# 4-Connectors.net
KiCad netlist of a schematic drawn in Altium Designer
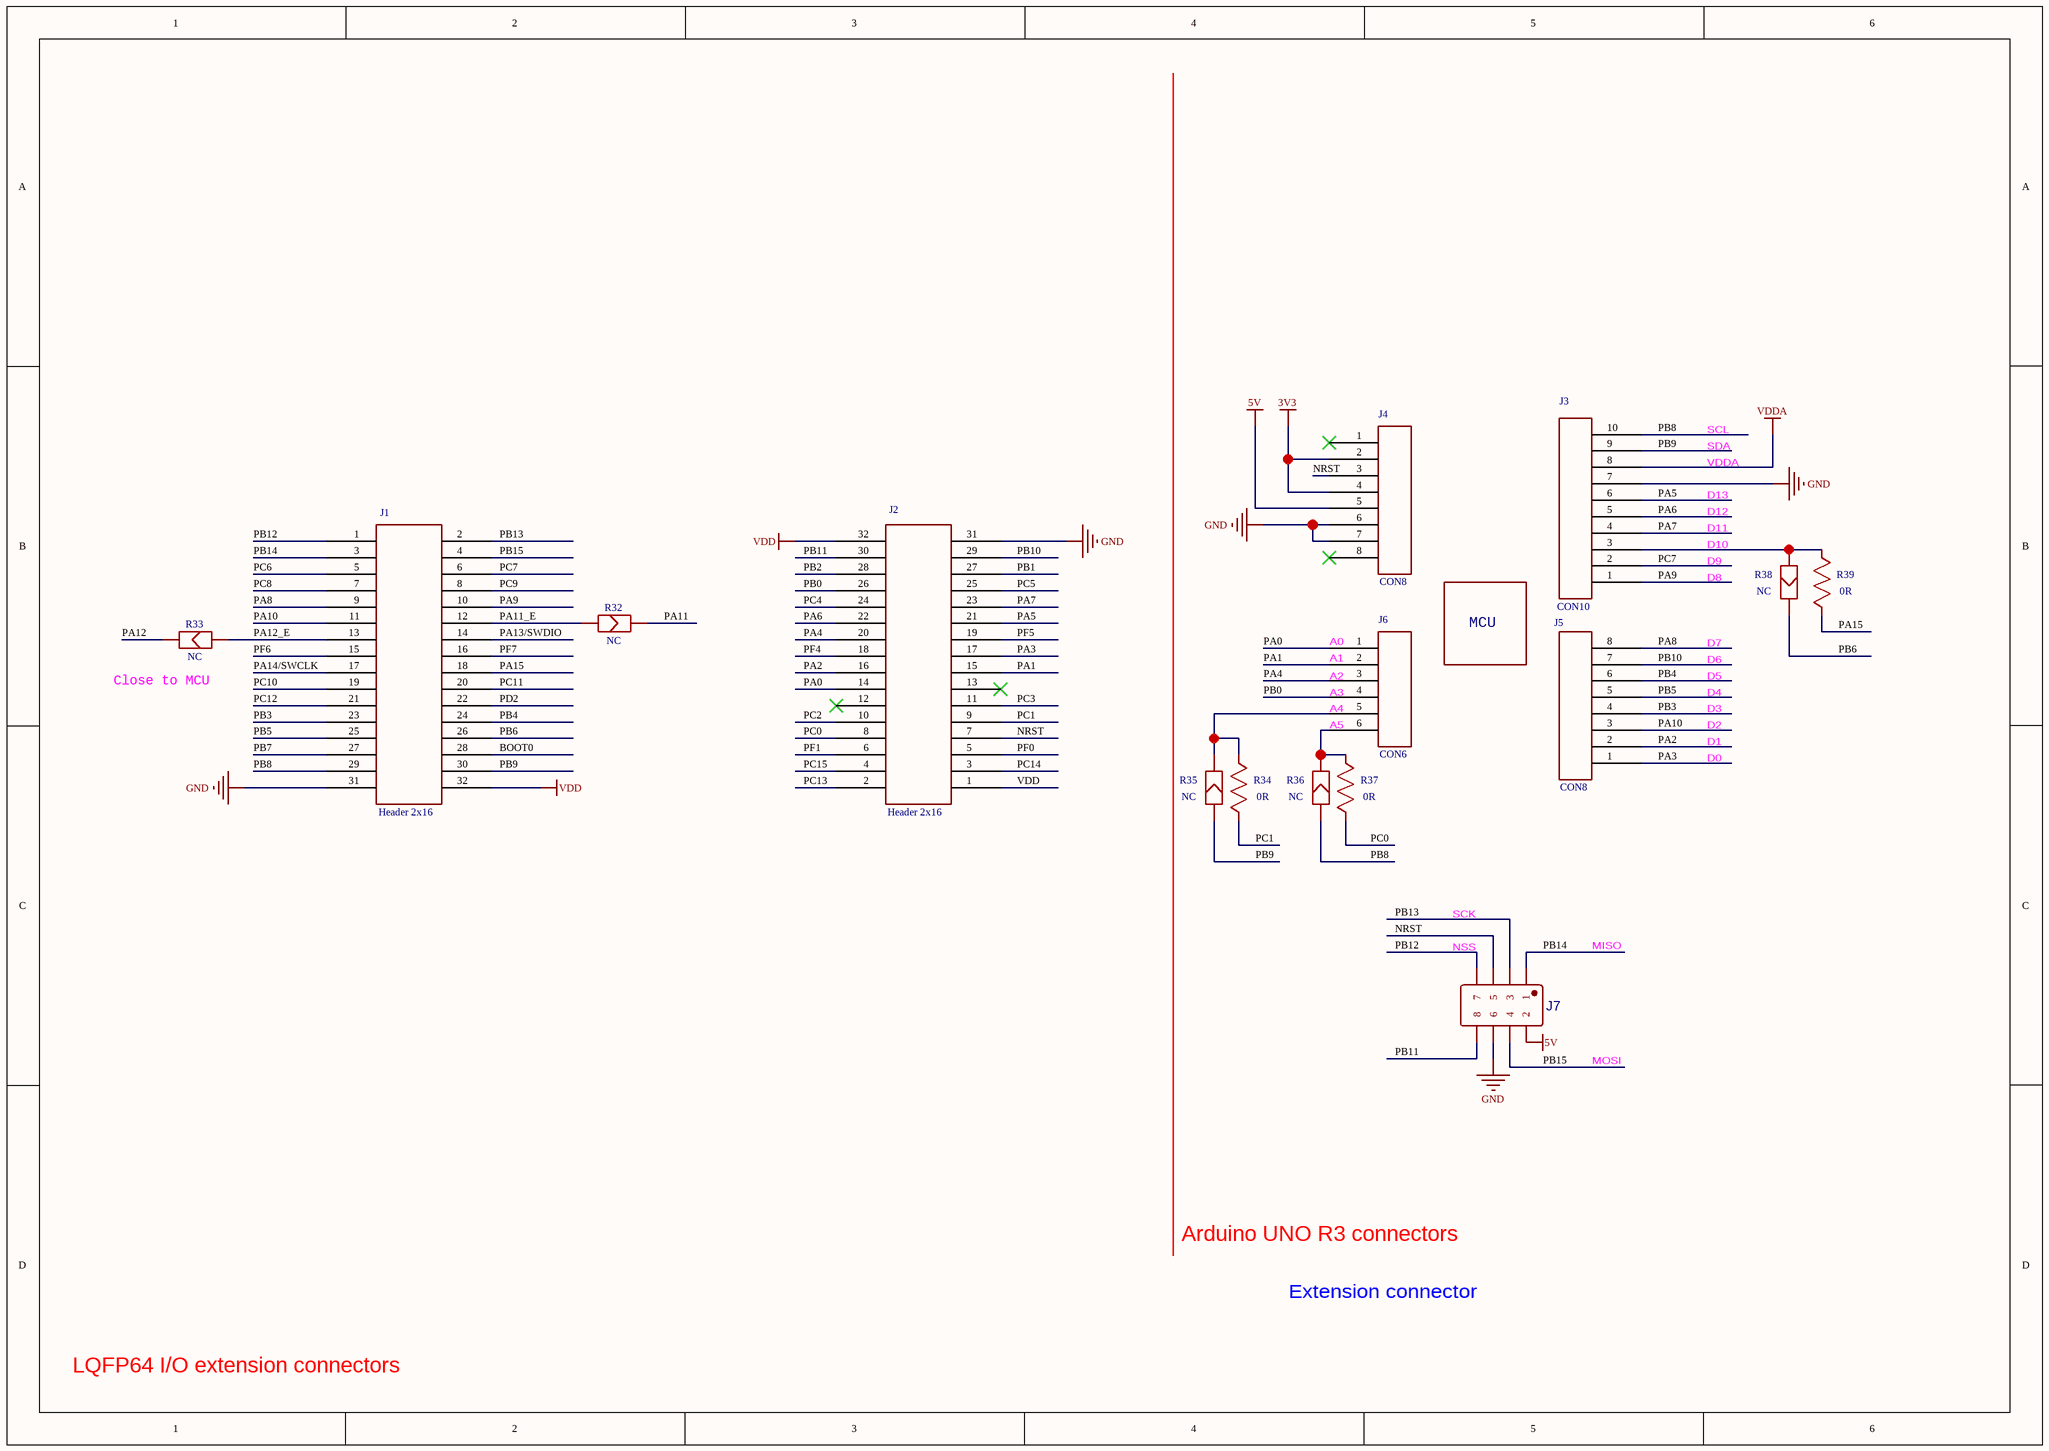
[diagram p0: 4-Connectors.schdoc]

(export (version "E")
  (design (tool "Eeschema 10.0.6"))
  (components
    (comp (ref "J1") (value "Header 2x16") (libsource (lib "altium-import") (part "root_0_Header 2x16_")))
    (comp (ref "J2") (value "Header 2x16") (libsource (lib "altium-import") (part "root_2_Header 2x16_")))
    (comp (ref "J3") (value "CON10") (libsource (lib "altium-import") (part "root_2_CON10_")))
    (comp (ref "J4") (value "CON8") (libsource (lib "altium-import") (part "root_0_CON8_")))
    (comp (ref "J5") (value "CON8") (libsource (lib "altium-import") (part "root_2_CON8_")))
    (comp (ref "J6") (value "CON6") (libsource (lib "altium-import") (part "root_0_CON6_")))
    (comp (ref "J7")
      (value "Header 4X2")
      (fields (field (name "PUBLISHER") "Altium Limited") (field (name "CONTRIBUTOR") "twb17"))
      (libsource (lib "altium-import") (part "root_3_Header 4X2_"))
    )
    (comp (ref "R32")
      (value "NC")
      (fields (field (name "CONTRIBUTOR") "twb17"))
      (libsource (lib "altium-import") (part "root_0_NC_"))
    )
    (comp (ref "R33")
      (value "NC")
      (fields (field (name "CONTRIBUTOR") "twb17"))
      (libsource (lib "altium-import") (part "root_2_NC_"))
    )
    (comp (ref "R34")
      (value "0R")
      (fields (field (name "CONTRIBUTOR") "LCEDA_Lib"))
      (libsource (lib "altium-import") (part "root_3_0R_"))
    )
    (comp (ref "R35")
      (value "NC")
      (fields (field (name "CONTRIBUTOR") "twb17"))
      (libsource (lib "altium-import") (part "root_1_NC_"))
    )
    (comp (ref "R36")
      (value "NC")
      (fields (field (name "CONTRIBUTOR") "twb17"))
      (libsource (lib "altium-import") (part "root_1_NC_"))
    )
    (comp (ref "R37")
      (value "0R")
      (fields (field (name "CONTRIBUTOR") "LCEDA_Lib"))
      (libsource (lib "altium-import") (part "root_3_0R_"))
    )
    (comp (ref "R38")
      (value "NC")
      (fields (field (name "CONTRIBUTOR") "twb17"))
      (libsource (lib "altium-import") (part "root_3_NC_"))
    )
    (comp (ref "R39")
      (value "0R")
      (fields (field (name "CONTRIBUTOR") "LCEDA_Lib"))
      (libsource (lib "altium-import") (part "root_3_0R_"))
    )
  )
  (nets
    (net (code "1") (name "/BOOT0") (class "Default")
      (node (ref "J1") (pin "28") (pinfunction "28_28") (pintype "passive"))
    )
    (net (code "2") (name "/NRST") (class "Default")
      (node (ref "J2") (pin "7") (pinfunction "7_7") (pintype "passive"))
      (node (ref "J4") (pin "3") (pinfunction "3_3") (pintype "passive"))
      (node (ref "J7") (pin "5") (pinfunction "5_5") (pintype "passive"))
    )
    (net (code "3") (name "/PA0") (class "Default")
      (node (ref "J2") (pin "14") (pinfunction "14_14") (pintype "passive"))
      (node (ref "J6") (pin "1") (pinfunction "1_1") (pintype "passive"))
    )
    (net (code "4") (name "/PA1") (class "Default")
      (node (ref "J2") (pin "15") (pinfunction "15_15") (pintype "passive"))
      (node (ref "J6") (pin "2") (pinfunction "2_2") (pintype "passive"))
    )
    (net (code "5") (name "/PA2") (class "Default")
      (node (ref "J2") (pin "16") (pinfunction "16_16") (pintype "passive"))
      (node (ref "J5") (pin "2") (pinfunction "2_2") (pintype "passive"))
    )
    (net (code "6") (name "/PA3") (class "Default")
      (node (ref "J2") (pin "17") (pinfunction "17_17") (pintype "passive"))
      (node (ref "J5") (pin "1") (pinfunction "1_1") (pintype "passive"))
    )
    (net (code "7") (name "/PA4") (class "Default")
      (node (ref "J2") (pin "20") (pinfunction "20_20") (pintype "passive"))
      (node (ref "J6") (pin "3") (pinfunction "3_3") (pintype "passive"))
    )
    (net (code "8") (name "/PA5") (class "Default")
      (node (ref "J2") (pin "21") (pinfunction "21_21") (pintype "passive"))
      (node (ref "J3") (pin "6") (pinfunction "6_6") (pintype "passive"))
    )
    (net (code "9") (name "/PA6") (class "Default")
      (node (ref "J2") (pin "22") (pinfunction "22_22") (pintype "passive"))
      (node (ref "J3") (pin "5") (pinfunction "5_5") (pintype "passive"))
    )
    (net (code "10") (name "/PA7") (class "Default")
      (node (ref "J2") (pin "23") (pinfunction "23_23") (pintype "passive"))
      (node (ref "J3") (pin "4") (pinfunction "4_4") (pintype "passive"))
    )
    (net (code "11") (name "/PA8") (class "Default")
      (node (ref "J1") (pin "9") (pinfunction "9_9") (pintype "passive"))
      (node (ref "J5") (pin "8") (pinfunction "8_8") (pintype "passive"))
    )
    (net (code "12") (name "/PA9") (class "Default")
      (node (ref "J1") (pin "10") (pinfunction "10_10") (pintype "passive"))
      (node (ref "J3") (pin "1") (pinfunction "1_1") (pintype "passive"))
    )
    (net (code "13") (name "/PA10") (class "Default")
      (node (ref "J1") (pin "11") (pinfunction "11_11") (pintype "passive"))
      (node (ref "J5") (pin "3") (pinfunction "3_3") (pintype "passive"))
    )
    (net (code "14") (name "/PA11") (class "Default")
      (node (ref "R32") (pin "2") (pinfunction "2_2") (pintype "passive"))
    )
    (net (code "15") (name "/PA11_E") (class "Default")
      (node (ref "J1") (pin "12") (pinfunction "12_12") (pintype "passive"))
      (node (ref "R32") (pin "1") (pinfunction "1_1") (pintype "passive"))
    )
    (net (code "16") (name "/PA12") (class "Default")
      (node (ref "R33") (pin "2") (pinfunction "2_2") (pintype "passive"))
    )
    (net (code "17") (name "/PA12_E") (class "Default")
      (node (ref "J1") (pin "13") (pinfunction "13_13") (pintype "passive"))
      (node (ref "R33") (pin "1") (pinfunction "1_1") (pintype "passive"))
    )
    (net (code "18") (name "/PA13{slash}SWDIO") (class "Default")
      (node (ref "J1") (pin "14") (pinfunction "14_14") (pintype "passive"))
    )
    (net (code "19") (name "/PA14{slash}SWCLK") (class "Default")
      (node (ref "J1") (pin "17") (pinfunction "17_17") (pintype "passive"))
    )
    (net (code "20") (name "/PA15") (class "Default")
      (node (ref "J1") (pin "18") (pinfunction "18_18") (pintype "passive"))
      (node (ref "R39") (pin "2") (pinfunction "2_2") (pintype "passive"))
    )
    (net (code "21") (name "/PB0") (class "Default")
      (node (ref "J2") (pin "26") (pinfunction "26_26") (pintype "passive"))
      (node (ref "J6") (pin "4") (pinfunction "4_4") (pintype "passive"))
    )
    (net (code "22") (name "/PB1") (class "Default")
      (node (ref "J2") (pin "27") (pinfunction "27_27") (pintype "passive"))
    )
    (net (code "23") (name "/PB2") (class "Default")
      (node (ref "J2") (pin "28") (pinfunction "28_28") (pintype "passive"))
    )
    (net (code "24") (name "/PB3") (class "Default")
      (node (ref "J1") (pin "23") (pinfunction "23_23") (pintype "passive"))
      (node (ref "J5") (pin "4") (pinfunction "4_4") (pintype "passive"))
    )
    (net (code "25") (name "/PB4") (class "Default")
      (node (ref "J1") (pin "24") (pinfunction "24_24") (pintype "passive"))
      (node (ref "J5") (pin "6") (pinfunction "6_6") (pintype "passive"))
    )
    (net (code "26") (name "/PB5") (class "Default")
      (node (ref "J1") (pin "25") (pinfunction "25_25") (pintype "passive"))
      (node (ref "J5") (pin "5") (pinfunction "5_5") (pintype "passive"))
    )
    (net (code "27") (name "/PB6") (class "Default")
      (node (ref "J1") (pin "26") (pinfunction "26_26") (pintype "passive"))
      (node (ref "R38") (pin "2") (pinfunction "2_2") (pintype "passive"))
    )
    (net (code "28") (name "/PB7") (class "Default")
      (node (ref "J1") (pin "27") (pinfunction "27_27") (pintype "passive"))
    )
    (net (code "29") (name "/PB8") (class "Default")
      (node (ref "J1") (pin "29") (pinfunction "29_29") (pintype "passive"))
      (node (ref "J3") (pin "10") (pinfunction "10_10") (pintype "passive"))
      (node (ref "R36") (pin "1") (pinfunction "1_1") (pintype "passive"))
    )
    (net (code "30") (name "/PB9") (class "Default")
      (node (ref "J1") (pin "30") (pinfunction "30_30") (pintype "passive"))
      (node (ref "J3") (pin "9") (pinfunction "9_9") (pintype "passive"))
      (node (ref "R35") (pin "1") (pinfunction "1_1") (pintype "passive"))
    )
    (net (code "31") (name "/PB10") (class "Default")
      (node (ref "J2") (pin "29") (pinfunction "29_29") (pintype "passive"))
      (node (ref "J5") (pin "7") (pinfunction "7_7") (pintype "passive"))
    )
    (net (code "32") (name "/PB11") (class "Default")
      (node (ref "J2") (pin "30") (pinfunction "30_30") (pintype "passive"))
      (node (ref "J7") (pin "8") (pinfunction "8_8") (pintype "passive"))
    )
    (net (code "33") (name "/PB12") (class "Default")
      (node (ref "J1") (pin "1") (pinfunction "1_1") (pintype "passive"))
      (node (ref "J7") (pin "7") (pinfunction "7_7") (pintype "passive"))
    )
    (net (code "34") (name "/PB13") (class "Default")
      (node (ref "J1") (pin "2") (pinfunction "2_2") (pintype "passive"))
      (node (ref "J7") (pin "3") (pinfunction "3_3") (pintype "passive"))
    )
    (net (code "35") (name "/PB14") (class "Default")
      (node (ref "J1") (pin "3") (pinfunction "3_3") (pintype "passive"))
      (node (ref "J7") (pin "1") (pinfunction "1_1") (pintype "passive"))
    )
    (net (code "36") (name "/PB15") (class "Default")
      (node (ref "J1") (pin "4") (pinfunction "4_4") (pintype "passive"))
      (node (ref "J7") (pin "4") (pinfunction "4_4") (pintype "passive"))
    )
    (net (code "37") (name "/PC0") (class "Default")
      (node (ref "J2") (pin "8") (pinfunction "8_8") (pintype "passive"))
      (node (ref "R37") (pin "2") (pinfunction "2_2") (pintype "passive"))
    )
    (net (code "38") (name "/PC1") (class "Default")
      (node (ref "J2") (pin "9") (pinfunction "9_9") (pintype "passive"))
      (node (ref "R34") (pin "2") (pinfunction "2_2") (pintype "passive"))
    )
    (net (code "39") (name "/PC2") (class "Default")
      (node (ref "J2") (pin "10") (pinfunction "10_10") (pintype "passive"))
    )
    (net (code "40") (name "/PC3") (class "Default")
      (node (ref "J2") (pin "11") (pinfunction "11_11") (pintype "passive"))
    )
    (net (code "41") (name "/PC4") (class "Default")
      (node (ref "J2") (pin "24") (pinfunction "24_24") (pintype "passive"))
    )
    (net (code "42") (name "/PC5") (class "Default")
      (node (ref "J2") (pin "25") (pinfunction "25_25") (pintype "passive"))
    )
    (net (code "43") (name "/PC6") (class "Default")
      (node (ref "J1") (pin "5") (pinfunction "5_5") (pintype "passive"))
    )
    (net (code "44") (name "/PC7") (class "Default")
      (node (ref "J1") (pin "6") (pinfunction "6_6") (pintype "passive"))
      (node (ref "J3") (pin "2") (pinfunction "2_2") (pintype "passive"))
    )
    (net (code "45") (name "/PC8") (class "Default")
      (node (ref "J1") (pin "7") (pinfunction "7_7") (pintype "passive"))
    )
    (net (code "46") (name "/PC9") (class "Default")
      (node (ref "J1") (pin "8") (pinfunction "8_8") (pintype "passive"))
    )
    (net (code "47") (name "/PC10") (class "Default")
      (node (ref "J1") (pin "19") (pinfunction "19_19") (pintype "passive"))
    )
    (net (code "48") (name "/PC11") (class "Default")
      (node (ref "J1") (pin "20") (pinfunction "20_20") (pintype "passive"))
    )
    (net (code "49") (name "/PC12") (class "Default")
      (node (ref "J1") (pin "21") (pinfunction "21_21") (pintype "passive"))
    )
    (net (code "50") (name "/PC13") (class "Default")
      (node (ref "J2") (pin "2") (pinfunction "2_2") (pintype "passive"))
    )
    (net (code "51") (name "/PC14") (class "Default")
      (node (ref "J2") (pin "3") (pinfunction "3_3") (pintype "passive"))
    )
    (net (code "52") (name "/PC15") (class "Default")
      (node (ref "J2") (pin "4") (pinfunction "4_4") (pintype "passive"))
    )
    (net (code "53") (name "/PD2") (class "Default")
      (node (ref "J1") (pin "22") (pinfunction "22_22") (pintype "passive"))
    )
    (net (code "54") (name "/PF0") (class "Default")
      (node (ref "J2") (pin "5") (pinfunction "5_5") (pintype "passive"))
    )
    (net (code "55") (name "/PF1") (class "Default")
      (node (ref "J2") (pin "6") (pinfunction "6_6") (pintype "passive"))
    )
    (net (code "56") (name "/PF4") (class "Default")
      (node (ref "J2") (pin "18") (pinfunction "18_18") (pintype "passive"))
    )
    (net (code "57") (name "/PF5") (class "Default")
      (node (ref "J2") (pin "19") (pinfunction "19_19") (pintype "passive"))
    )
    (net (code "58") (name "/PF6") (class "Default")
      (node (ref "J1") (pin "15") (pinfunction "15_15") (pintype "passive"))
    )
    (net (code "59") (name "/PF7") (class "Default")
      (node (ref "J1") (pin "16") (pinfunction "16_16") (pintype "passive"))
    )
    (net (code "60") (name "3V3") (class "Default")
      (node (ref "J4") (pin "2") (pinfunction "2_2") (pintype "passive"))
      (node (ref "J4") (pin "4") (pinfunction "4_4") (pintype "passive"))
    )
    (net (code "61") (name "5V") (class "Default")
      (node (ref "J4") (pin "5") (pinfunction "5_5") (pintype "passive"))
      (node (ref "J7") (pin "2") (pinfunction "2_2") (pintype "passive"))
    )
    (net (code "62") (name "GND") (class "Default")
      (node (ref "J1") (pin "31") (pinfunction "31_31") (pintype "passive"))
      (node (ref "J2") (pin "31") (pinfunction "31_31") (pintype "passive"))
      (node (ref "J3") (pin "7") (pinfunction "7_7") (pintype "passive"))
      (node (ref "J4") (pin "6") (pinfunction "6_6") (pintype "passive"))
      (node (ref "J4") (pin "7") (pinfunction "7_7") (pintype "passive"))
      (node (ref "J7") (pin "6") (pinfunction "6_6") (pintype "passive"))
    )
    (net (code "63") (name "Net-(J3-Pad3)") (class "Default")
      (node (ref "J3") (pin "3") (pinfunction "3_3") (pintype "passive"))
      (node (ref "R38") (pin "1") (pinfunction "1_1") (pintype "passive"))
      (node (ref "R39") (pin "1") (pinfunction "1_1") (pintype "passive"))
    )
    (net (code "64") (name "Net-(J6-Pad5)") (class "Default")
      (node (ref "J6") (pin "5") (pinfunction "5_5") (pintype "passive"))
      (node (ref "R34") (pin "1") (pinfunction "1_1") (pintype "passive"))
      (node (ref "R35") (pin "2") (pinfunction "2_2") (pintype "passive"))
    )
    (net (code "65") (name "Net-(J6-Pad6)") (class "Default")
      (node (ref "J6") (pin "6") (pinfunction "6_6") (pintype "passive"))
      (node (ref "R36") (pin "2") (pinfunction "2_2") (pintype "passive"))
      (node (ref "R37") (pin "1") (pinfunction "1_1") (pintype "passive"))
    )
    (net (code "66") (name "VDD") (class "Default")
      (node (ref "J1") (pin "32") (pinfunction "32_32") (pintype "passive"))
      (node (ref "J2") (pin "1") (pinfunction "1_1") (pintype "passive"))
      (node (ref "J2") (pin "32") (pinfunction "32_32") (pintype "passive"))
    )
    (net (code "67") (name "VDDA") (class "Default")
      (node (ref "J3") (pin "8") (pinfunction "8_8") (pintype "passive"))
    )
    (net (code "68") (name "unconnected-(J2-Pad12)") (class "Default")
      (node (ref "J2") (pin "12") (pinfunction "12_12") (pintype "passive+no_connect"))
    )
    (net (code "69") (name "unconnected-(J2-Pad13)") (class "Default")
      (node (ref "J2") (pin "13") (pinfunction "13_13") (pintype "passive+no_connect"))
    )
    (net (code "70") (name "unconnected-(J4-Pad1)") (class "Default")
      (node (ref "J4") (pin "1") (pinfunction "1_1") (pintype "passive+no_connect"))
    )
    (net (code "71") (name "unconnected-(J4-Pad8)") (class "Default")
      (node (ref "J4") (pin "8") (pinfunction "8_8") (pintype "passive+no_connect"))
    )
  )
)
